# Hobots-A-Coach-405.net
KiCad netlist of a schematic drawn in Altium Designer
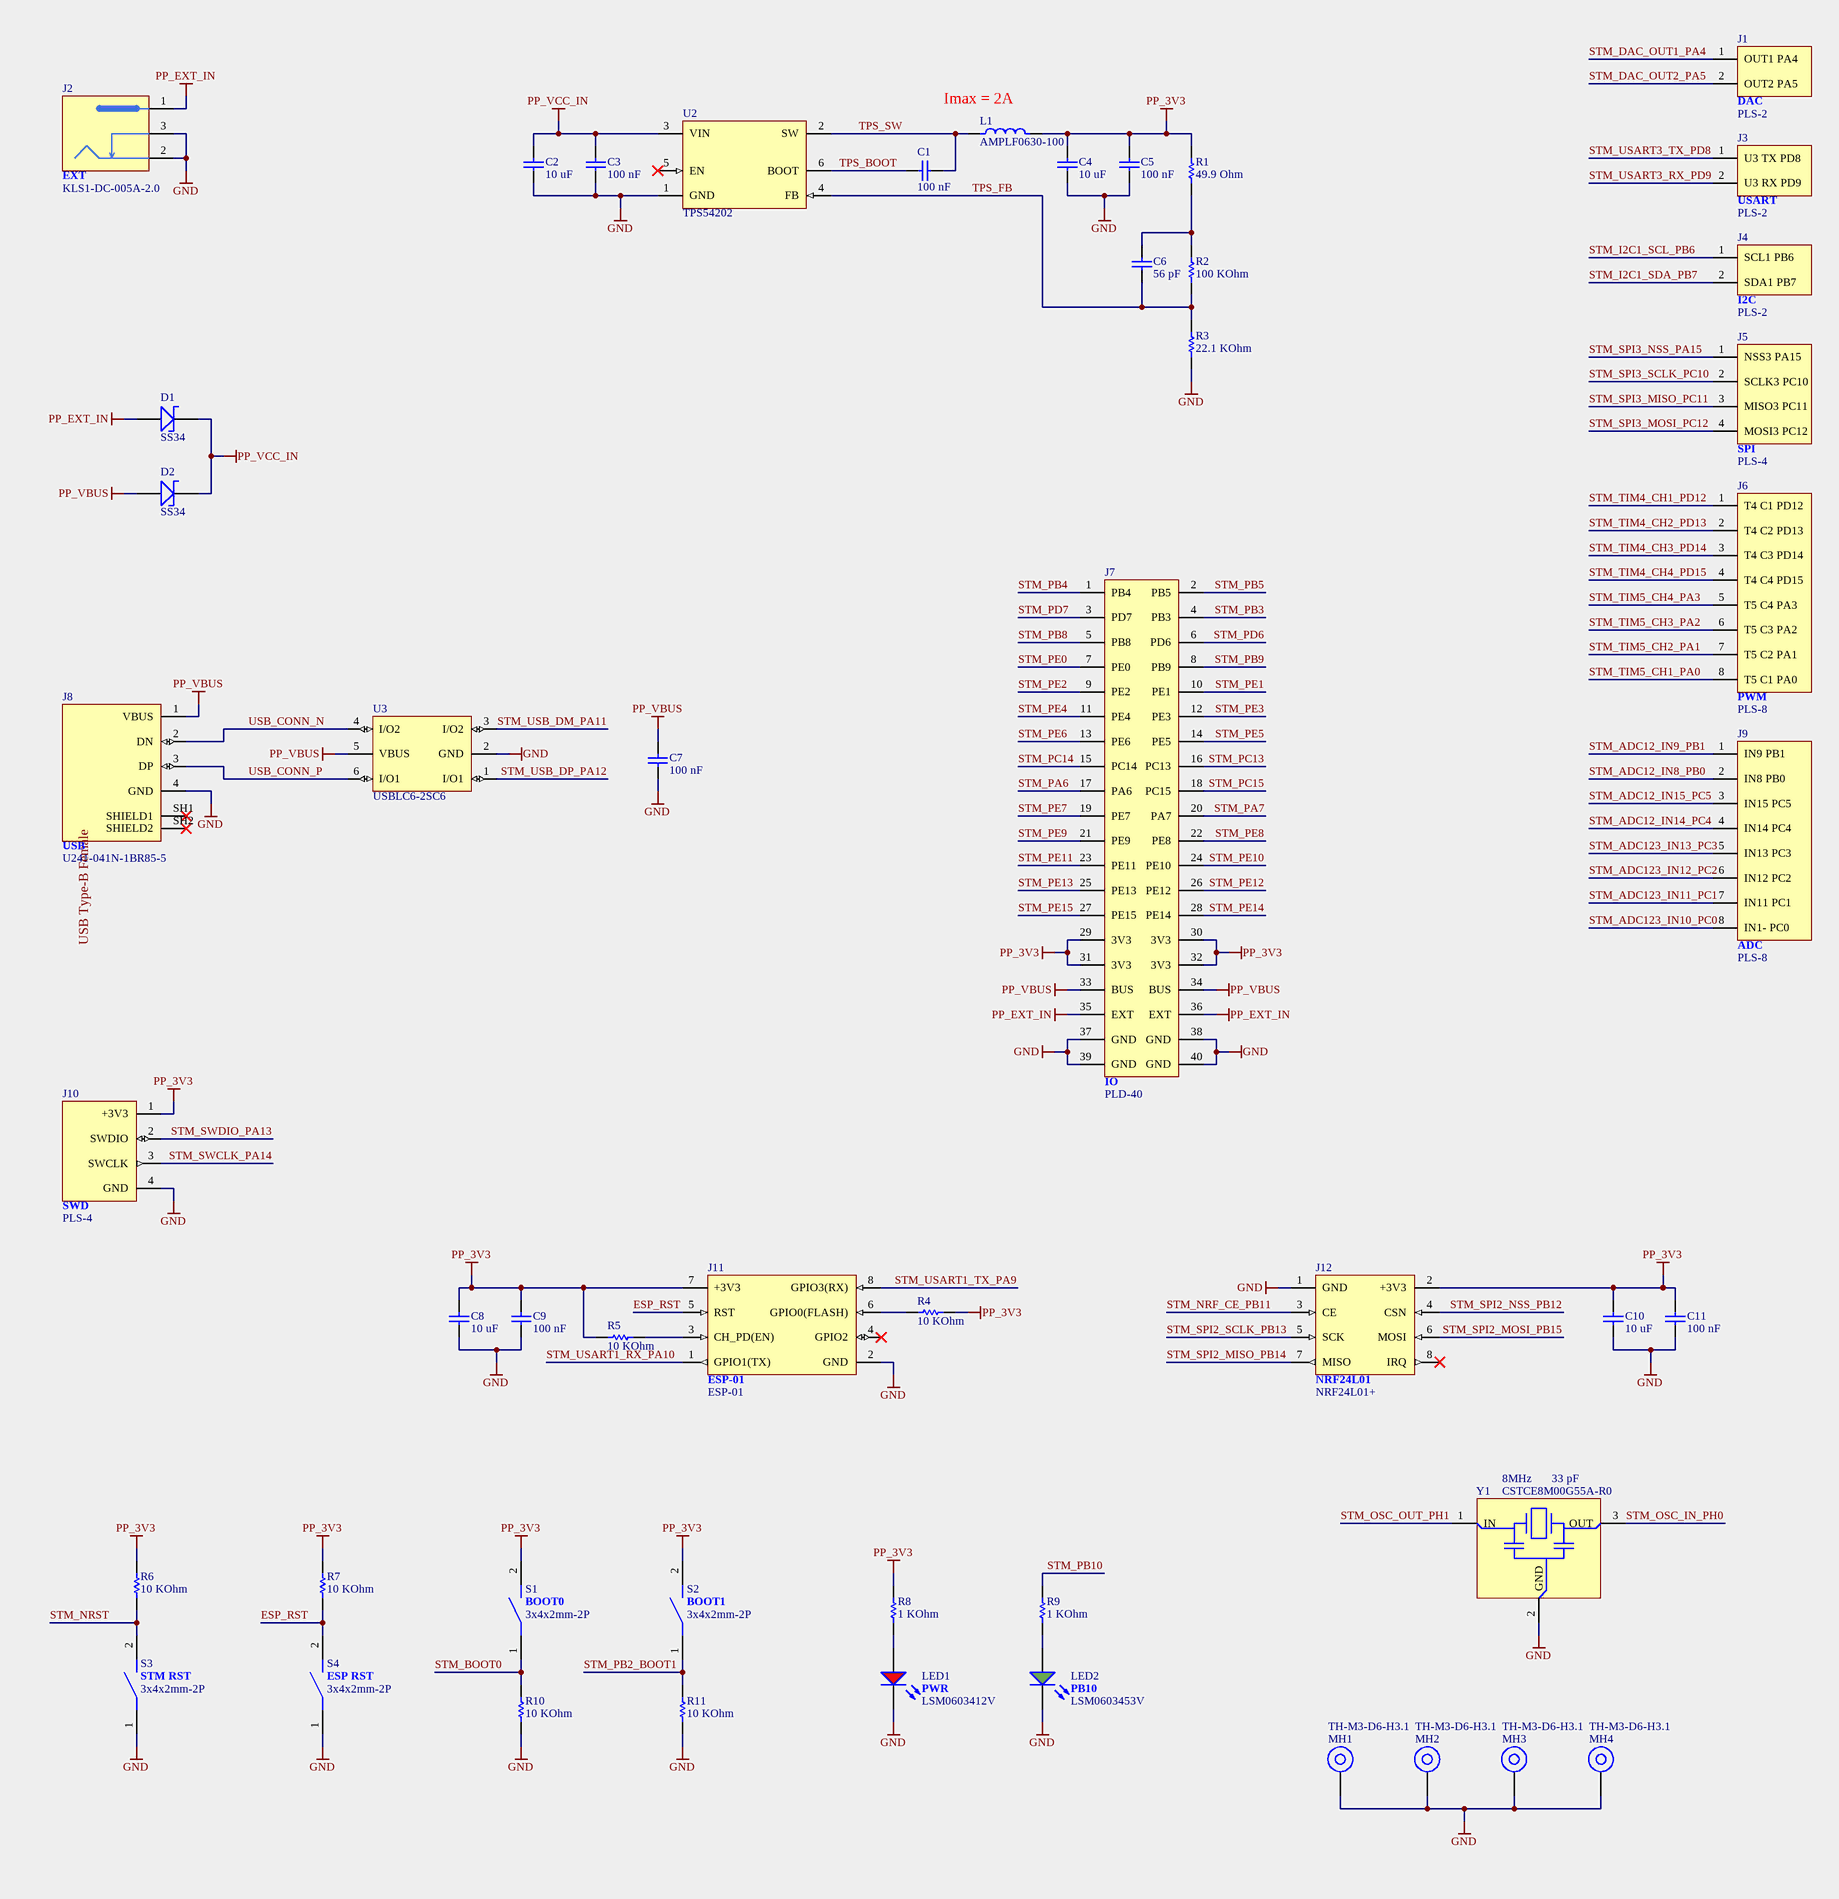
[diagram p0: Hobots-A-Coach-405.SchDoc, left]
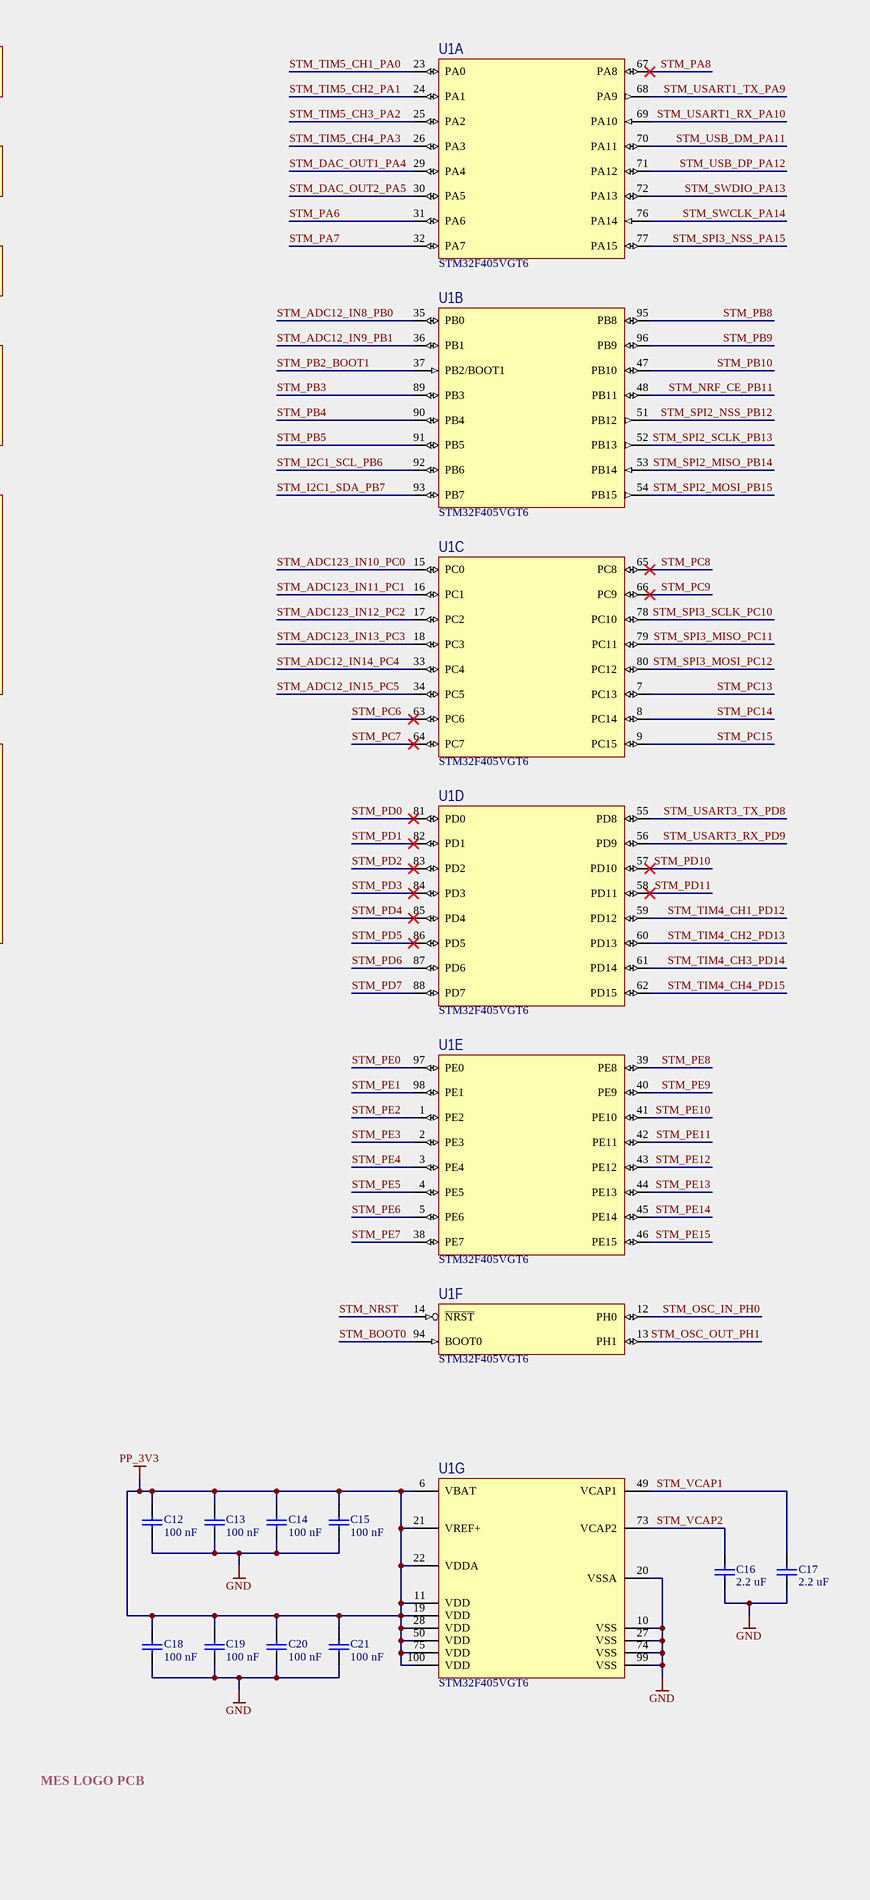
[diagram p1: Hobots-A-Coach-405.SchDoc, right]

(export (version "E")
  (design (tool "Eeschema 10.0.6"))
  (components
    (comp (ref "C1")
      (value "CAP-100N")
      (footprint "CAPC0603")
      (description "Chip Capacitor, 100 nF, +/- 5%")
      (fields (field (name "TOLERANCE") "5 %") (field (name "CAPACITANCE") "100 nF"))
      (libsource (lib "Конденсаторы керамические SMD") (part "CAP-100N"))
    )
    (comp (ref "C2")
      (value "CAP-10U")
      (footprint "CAPC0603")
      (description "Chip Capacitor, 10 uF, +/- 5%")
      (fields (field (name "TOLERANCE") "5 %") (field (name "CAPACITANCE") "10 uF"))
      (libsource (lib "Конденсаторы керамические SMD") (part "CAP-10U"))
    )
    (comp (ref "C3")
      (value "CAP-100N")
      (footprint "CAPC0603")
      (description "Chip Capacitor, 100 nF, +/- 5%")
      (fields (field (name "TOLERANCE") "5 %") (field (name "CAPACITANCE") "100 nF"))
      (libsource (lib "Конденсаторы керамические SMD") (part "CAP-100N"))
    )
    (comp (ref "C4")
      (value "CAP-10U")
      (footprint "CAPC0603")
      (description "Chip Capacitor, 10 uF, +/- 5%")
      (fields (field (name "TOLERANCE") "5 %") (field (name "CAPACITANCE") "10 uF"))
      (libsource (lib "Конденсаторы керамические SMD") (part "CAP-10U"))
    )
    (comp (ref "C5")
      (value "CAP-100N")
      (footprint "CAPC0603")
      (description "Chip Capacitor, 100 nF, +/- 5%")
      (fields (field (name "TOLERANCE") "5 %") (field (name "CAPACITANCE") "100 nF"))
      (libsource (lib "Конденсаторы керамические SMD") (part "CAP-100N"))
    )
    (comp (ref "C6")
      (value "CAP-56P")
      (footprint "CAPC0603")
      (description "Chip Capacitor, 56 pF, +/- 5%")
      (fields (field (name "TOLERANCE") "5 %") (field (name "CAPACITANCE") "56 pF"))
      (libsource (lib "Конденсаторы керамические SMD") (part "CAP-56P"))
    )
    (comp (ref "C7")
      (value "CAP-100N")
      (footprint "CAPC0603")
      (description "Chip Capacitor, 100 nF, +/- 5%")
      (fields (field (name "TOLERANCE") "5 %") (field (name "CAPACITANCE") "100 nF"))
      (libsource (lib "Конденсаторы керамические SMD") (part "CAP-100N"))
    )
    (comp (ref "C8")
      (value "CAP-10U")
      (footprint "CAPC0603")
      (description "Chip Capacitor, 10 uF, +/- 5%")
      (fields (field (name "TOLERANCE") "5 %") (field (name "CAPACITANCE") "10 uF"))
      (libsource (lib "Конденсаторы керамические SMD") (part "CAP-10U"))
    )
    (comp (ref "C9")
      (value "CAP-100N")
      (footprint "CAPC0603")
      (description "Chip Capacitor, 100 nF, +/- 5%")
      (fields (field (name "TOLERANCE") "5 %") (field (name "CAPACITANCE") "100 nF"))
      (libsource (lib "Конденсаторы керамические SMD") (part "CAP-100N"))
    )
    (comp (ref "C10")
      (value "CAP-10U")
      (footprint "CAPC0603")
      (description "Chip Capacitor, 10 uF, +/- 5%")
      (fields (field (name "TOLERANCE") "5 %") (field (name "CAPACITANCE") "10 uF"))
      (libsource (lib "Конденсаторы керамические SMD") (part "CAP-10U"))
    )
    (comp (ref "C11")
      (value "CAP-100N")
      (footprint "CAPC0603")
      (description "Chip Capacitor, 100 nF, +/- 5%")
      (fields (field (name "TOLERANCE") "5 %") (field (name "CAPACITANCE") "100 nF"))
      (libsource (lib "Конденсаторы керамические SMD") (part "CAP-100N"))
    )
    (comp (ref "C12")
      (value "CAP-100N")
      (footprint "CAPC0603")
      (description "Chip Capacitor, 100 nF, +/- 5%")
      (fields (field (name "TOLERANCE") "5 %") (field (name "CAPACITANCE") "100 nF"))
      (libsource (lib "Конденсаторы керамические SMD") (part "CAP-100N"))
    )
    (comp (ref "C13")
      (value "CAP-100N")
      (footprint "CAPC0603")
      (description "Chip Capacitor, 100 nF, +/- 5%")
      (fields (field (name "TOLERANCE") "5 %") (field (name "CAPACITANCE") "100 nF"))
      (libsource (lib "Конденсаторы керамические SMD") (part "CAP-100N"))
    )
    (comp (ref "C14")
      (value "CAP-100N")
      (footprint "CAPC0603")
      (description "Chip Capacitor, 100 nF, +/- 5%")
      (fields (field (name "TOLERANCE") "5 %") (field (name "CAPACITANCE") "100 nF"))
      (libsource (lib "Конденсаторы керамические SMD") (part "CAP-100N"))
    )
    (comp (ref "C15")
      (value "CAP-100N")
      (footprint "CAPC0603")
      (description "Chip Capacitor, 100 nF, +/- 5%")
      (fields (field (name "TOLERANCE") "5 %") (field (name "CAPACITANCE") "100 nF"))
      (libsource (lib "Конденсаторы керамические SMD") (part "CAP-100N"))
    )
    (comp (ref "C16")
      (value "CAP-2U2")
      (footprint "CAPC0603")
      (description "Chip Capacitor, 2.2 uF, +/- 5")
      (fields (field (name "TOLERANCE") "5 %") (field (name "CAPACITANCE") "2.2 uF"))
      (libsource (lib "Конденсаторы керамические SMD") (part "CAP-2U2"))
    )
    (comp (ref "C17")
      (value "CAP-2U2")
      (footprint "CAPC0603")
      (description "Chip Capacitor, 2.2 uF, +/- 5")
      (fields (field (name "TOLERANCE") "5 %") (field (name "CAPACITANCE") "2.2 uF"))
      (libsource (lib "Конденсаторы керамические SMD") (part "CAP-2U2"))
    )
    (comp (ref "C18")
      (value "CAP-100N")
      (footprint "CAPC0603")
      (description "Chip Capacitor, 100 nF, +/- 5%")
      (fields (field (name "TOLERANCE") "5 %") (field (name "CAPACITANCE") "100 nF"))
      (libsource (lib "Конденсаторы керамические SMD") (part "CAP-100N"))
    )
    (comp (ref "C19")
      (value "CAP-100N")
      (footprint "CAPC0603")
      (description "Chip Capacitor, 100 nF, +/- 5%")
      (fields (field (name "TOLERANCE") "5 %") (field (name "CAPACITANCE") "100 nF"))
      (libsource (lib "Конденсаторы керамические SMD") (part "CAP-100N"))
    )
    (comp (ref "C20")
      (value "CAP-100N")
      (footprint "CAPC0603")
      (description "Chip Capacitor, 100 nF, +/- 5%")
      (fields (field (name "TOLERANCE") "5 %") (field (name "CAPACITANCE") "100 nF"))
      (libsource (lib "Конденсаторы керамические SMD") (part "CAP-100N"))
    )
    (comp (ref "C21")
      (value "CAP-100N")
      (footprint "CAPC0603")
      (description "Chip Capacitor, 100 nF, +/- 5%")
      (fields (field (name "TOLERANCE") "5 %") (field (name "CAPACITANCE") "100 nF"))
      (libsource (lib "Конденсаторы керамические SMD") (part "CAP-100N"))
    )
    (comp (ref "D1")
      (value "SS34")
      (footprint "DO-214AC(SMA)")
      (description "40V 3A Low forward voltage drop. High current capability Schottky Diode.")
      (fields (field (name "PARTNUMBER") "SS34"))
      (libsource (lib "Диоды выпрямительные") (part "SS34"))
    )
    (comp (ref "D2")
      (value "SS34")
      (footprint "DO-214AC(SMA)")
      (description "40V 3A Low forward voltage drop. High current capability Schottky Diode.")
      (fields (field (name "PARTNUMBER") "SS34"))
      (libsource (lib "Диоды выпрямительные") (part "SS34"))
    )
    (comp (ref "G1")
      (value "MES Logo")
      (footprint "MES_LOGO_COPPER_3MM")
      (description "Logotips MES GROUP")
      (libsource (lib "Знаки") (part "MES Logo"))
    )
    (comp (ref "J1")
      (value "DAC")
      (footprint "PLS-2")
      (description "pitch 2.54")
      (fields (field (name "PARTNUMBER") "PLS-2"))
      (libsource (lib "Разъемы") (part "PLS-2"))
    )
    (comp (ref "J2")
      (value "EXT")
      (footprint "KLS1-DC-005")
      (description "5.5mm 2.0mm 2A 16V")
      (fields (field (name "PARTNUMBER") "KLS1-DC-005A-2.0"))
      (libsource (lib "Разъемы") (part "KLS1-DC-005A-2.0"))
    )
    (comp (ref "J3")
      (value "USART")
      (footprint "PLS-2")
      (description "pitch 2.54")
      (fields (field (name "PARTNUMBER") "PLS-2"))
      (libsource (lib "Разъемы") (part "PLS-2"))
    )
    (comp (ref "J4")
      (value "I2C")
      (footprint "PLS-2")
      (description "pitch 2.54")
      (fields (field (name "PARTNUMBER") "PLS-2"))
      (libsource (lib "Разъемы") (part "PLS-2"))
    )
    (comp (ref "J5")
      (value "SPI")
      (footprint "PLS-4")
      (description "pitch 2.54")
      (fields (field (name "PARTNUMBER") "PLS-4"))
      (libsource (lib "Разъемы") (part "PLS-4"))
    )
    (comp (ref "J6")
      (value "PWM")
      (footprint "PLS-8")
      (description "pitch 2.54")
      (fields (field (name "PARTNUMBER") "PLS-8"))
      (libsource (lib "Разъемы") (part "PLS-8"))
    )
    (comp (ref "J7")
      (value "IO")
      (footprint "PLD-40")
      (description "2 row, pitch 2.54")
      (fields (field (name "PARTNUMBER") "PLD-40"))
      (libsource (lib "Разъемы") (part "PLD-40"))
    )
    (comp (ref "J8")
      (value "USB")
      (footprint "U241-041N-1BR85-5")
      (description "USB - Type B Female USB 2 4 Through Hole USB Connectors")
      (fields (field (name "PARTNUMBER") "U241-041N-1BR85-5"))
      (libsource (lib "Разъемы") (part "USB-B U241-041N-1BR85-5"))
    )
    (comp (ref "J9")
      (value "ADC")
      (footprint "PLS-8")
      (description "pitch 2.54")
      (fields (field (name "PARTNUMBER") "PLS-8"))
      (libsource (lib "Разъемы") (part "PLS-8"))
    )
    (comp (ref "J10")
      (value "SWD")
      (footprint "PLS-4")
      (description "STM SWD 4 pin")
      (fields (field (name "PARTNUMBER") "PLS-4"))
      (libsource (lib "Разъемы") (part "SWD-PLS4"))
    )
    (comp (ref "J11")
      (value "ESP-01")
      (footprint "ESP-01 Socket")
      (description "Socket for ESP8266 ESP-01 Connector PBD 8 pins 2x4 pitch 2.54")
      (fields (field (name "PARTNUMBER") "ESP-01"))
      (libsource (lib "Разъемы") (part "ESP-01 Socket"))
    )
    (comp (ref "J12")
      (value "NRF24L01")
      (footprint "NRF24L01+ Socket")
      (description "Socket for NRF24L01 / NRF24L01+ Connector PBD 8 pins 2x4 pitch 2.54")
      (fields (field (name "PARTNUMBER") "NRF24L01+"))
      (libsource (lib "Разъемы") (part "NRF24L01+ Socket"))
    )
    (comp (ref "L1")
      (value "AMPLF0630-100")
      (footprint "AMPLF0630")
      (description "Shielded Power Inductor 10μH ± 20%")
      (fields (field (name "PARTNUMBER") "AMPLF0630-100"))
      (libsource (lib "Индуктивности") (part "AMPLF0630-100"))
    )
    (comp (ref "LED1")
      (value "PWR")
      (footprint "LSM0603-Series")
      (description "Red LED 0603 2V 20mA")
      (fields (field (name "PARTNUMBER") "LSM0603412V"))
      (libsource (lib "Светодиоды") (part "LSM0603412V"))
    )
    (comp (ref "LED2")
      (value "PB10")
      (footprint "LSM0603-Series")
      (description "Green LED 0603 3V 20mA")
      (fields (field (name "PARTNUMBER") "LSM0603453V"))
      (libsource (lib "Светодиоды") (part "LSM0603453V"))
    )
    (comp (ref "MH1")
      (value "TH-M3-D6-H3.1")
      (footprint "TH-M3-D6-H3.1")
      (libsource (lib "Отверстия") (part "TH-M3-D6-H3.1"))
    )
    (comp (ref "MH2")
      (value "TH-M3-D6-H3.1")
      (footprint "TH-M3-D6-H3.1")
      (libsource (lib "Отверстия") (part "TH-M3-D6-H3.1"))
    )
    (comp (ref "MH3")
      (value "TH-M3-D6-H3.1")
      (footprint "TH-M3-D6-H3.1")
      (libsource (lib "Отверстия") (part "TH-M3-D6-H3.1"))
    )
    (comp (ref "MH4")
      (value "TH-M3-D6-H3.1")
      (footprint "TH-M3-D6-H3.1")
      (libsource (lib "Отверстия") (part "TH-M3-D6-H3.1"))
    )
    (comp (ref "R1")
      (value "RES-49R9")
      (footprint "RES0603")
      (description "Chip Resistor, 49.9 Ohm, +/- 1%")
      (fields (field (name "TOLERANCE") "1 %") (field (name "RESISTANCE") "49.9 Ohm"))
      (libsource (lib "Резисторы SMD") (part "RES-49R9"))
    )
    (comp (ref "R2")
      (value "RES-100K")
      (footprint "RES0603")
      (description "Chip Resistor, 100 KOhm, +/- 1%")
      (fields (field (name "TOLERANCE") "1 %") (field (name "RESISTANCE") "100 KOhm"))
      (libsource (lib "Резисторы SMD") (part "RES-100K"))
    )
    (comp (ref "R3")
      (value "RES-22K1")
      (footprint "RES0603")
      (description "Chip Resistor, 22.1 KOhm, +/- 1%")
      (fields (field (name "TOLERANCE") "1 %") (field (name "RESISTANCE") "22.1 KOhm"))
      (libsource (lib "Резисторы SMD") (part "RES-22K1"))
    )
    (comp (ref "R4")
      (value "RES-10K")
      (footprint "RES0603")
      (description "Chip Resistor, 10 KOhm, +/- 1%")
      (fields (field (name "TOLERANCE") "1 %") (field (name "RESISTANCE") "10 KOhm"))
      (libsource (lib "Резисторы SMD") (part "RES-10K"))
    )
    (comp (ref "R5")
      (value "RES-10K")
      (footprint "RES0603")
      (description "Chip Resistor, 10 KOhm, +/- 1%")
      (fields (field (name "TOLERANCE") "1 %") (field (name "RESISTANCE") "10 KOhm"))
      (libsource (lib "Резисторы SMD") (part "RES-10K"))
    )
    (comp (ref "R6")
      (value "RES-10K")
      (footprint "RES0603")
      (description "Chip Resistor, 10 KOhm, +/- 1%")
      (fields (field (name "TOLERANCE") "1 %") (field (name "RESISTANCE") "10 KOhm"))
      (libsource (lib "Резисторы SMD") (part "RES-10K"))
    )
    (comp (ref "R7")
      (value "RES-10K")
      (footprint "RES0603")
      (description "Chip Resistor, 10 KOhm, +/- 1%")
      (fields (field (name "TOLERANCE") "1 %") (field (name "RESISTANCE") "10 KOhm"))
      (libsource (lib "Резисторы SMD") (part "RES-10K"))
    )
    (comp (ref "R8")
      (value "RES-1K")
      (footprint "RES0603")
      (description "Chip Resistor, 1 KOhm, +/- 1%")
      (fields (field (name "TOLERANCE") "1 %") (field (name "RESISTANCE") "1 KOhm"))
      (libsource (lib "Резисторы SMD") (part "RES-1K"))
    )
    (comp (ref "R9")
      (value "RES-1K")
      (footprint "RES0603")
      (description "Chip Resistor, 1 KOhm, +/- 1%")
      (fields (field (name "TOLERANCE") "1 %") (field (name "RESISTANCE") "1 KOhm"))
      (libsource (lib "Резисторы SMD") (part "RES-1K"))
    )
    (comp (ref "R10")
      (value "RES-10K")
      (footprint "RES0603")
      (description "Chip Resistor, 10 KOhm, +/- 1%")
      (fields (field (name "TOLERANCE") "1 %") (field (name "RESISTANCE") "10 KOhm"))
      (libsource (lib "Резисторы SMD") (part "RES-10K"))
    )
    (comp (ref "R11")
      (value "RES-10K")
      (footprint "RES0603")
      (description "Chip Resistor, 10 KOhm, +/- 1%")
      (fields (field (name "TOLERANCE") "1 %") (field (name "RESISTANCE") "10 KOhm"))
      (libsource (lib "Резисторы SMD") (part "RES-10K"))
    )
    (comp (ref "S1")
      (value "BOOT0")
      (footprint "Tactile Switch SMD 3x4x2-2p")
      (description "2-Pin SMD Tactile Switch, sunrom 3x4x2mm 12V DC 0.2A")
      (fields (field (name "MODEL") "3x4x2mm-2P"))
      (libsource (lib "Кнопки") (part "Tactile Switch 2P 3x4x2"))
    )
    (comp (ref "S2")
      (value "BOOT1")
      (footprint "Tactile Switch SMD 3x4x2-2p")
      (description "2-Pin SMD Tactile Switch, sunrom 3x4x2mm 12V DC 0.2A")
      (fields (field (name "MODEL") "3x4x2mm-2P"))
      (libsource (lib "Кнопки") (part "Tactile Switch 2P 3x4x2"))
    )
    (comp (ref "S3")
      (value "STM RST")
      (footprint "Tactile Switch SMD 3x4x2-2p")
      (description "2-Pin SMD Tactile Switch, sunrom 3x4x2mm 12V DC 0.2A")
      (fields (field (name "MODEL") "3x4x2mm-2P"))
      (libsource (lib "Кнопки") (part "Tactile Switch 2P 3x4x2"))
    )
    (comp (ref "S4")
      (value "ESP RST")
      (footprint "Tactile Switch SMD 3x4x2-2p")
      (description "2-Pin SMD Tactile Switch, sunrom 3x4x2mm 12V DC 0.2A")
      (fields (field (name "MODEL") "3x4x2mm-2P"))
      (libsource (lib "Кнопки") (part "Tactile Switch 2P 3x4x2"))
    )
    (comp (ref "U1")
      (value "STM32F405VGT6")
      (footprint "LQFP-100-STM32")
      (description "1024 KB Flash 192 RAM 168 MHz ARM based 32-bit MCU")
      (fields (field (name "PARTNUMBER") "STM32F405VGT6"))
      (libsource (lib "Микроконтроллеры") (part "STM32F405VGT6"))
    )
    (comp (ref "U2")
      (value "TPS54202")
      (footprint "SOT23-6-TI-TPS54202")
      (description "4.5-V to 28-V Input, 2-A Output, EMI Friendly\r\nSynchronous Step Down Converter")
      (fields (field (name "PARTNUMBER") "TPS54202"))
      (libsource (lib "Регуляторы напряжения") (part "TPS54202"))
    )
    (comp (ref "U3")
      (value "USBLC6-2SC6")
      (footprint "SOT23-6L-STM")
      (fields (field (name "PARTNUMBER") "USBLC6-2SC6"))
      (libsource (lib "Диоды TVS") (part "USBLC6-2SC6"))
    )
    (comp (ref "Y1")
      (value "CSTCE8M00G55A-R0")
      (footprint "MURATA_3213")
      (description "8MHz ±0.5% 33pF 40 Ohm(Max) SMDCrystal Resonators")
      (fields
        (field (name "LOADCAPACITANCE") "33 pF")
        (field (name "FREQUENCY") "8MHz")
        (field (name "PARTNUMBER") "CSTCE8M00G55A-R0")
      )
      (libsource (lib "Кварцы") (part "CSTCE8M00G55A-R0"))
    )
  )
  (nets
    (net (code "1") (name "/ESP_RST") (class "Default")
      (node (ref "J11") (pin "5") (pinfunction "RST_5") (pintype "input"))
      (node (ref "R7") (pin "1") (pinfunction "1_1") (pintype "passive"))
      (node (ref "S4") (pin "2") (pintype "passive"))
    )
    (net (code "2") (name "/STM_ADC12_IN8_PB0") (class "Default")
      (node (ref "J9") (pin "2") (pinfunction "T4_C2_PD13_2") (pintype "passive"))
      (node (ref "U1") (pin "35") (pinfunction "PB0_35") (pintype "bidirectional"))
    )
    (net (code "3") (name "/STM_ADC12_IN9_PB1") (class "Default")
      (node (ref "J9") (pin "1") (pinfunction "T4_C1_PD12_1") (pintype "passive"))
      (node (ref "U1") (pin "36") (pinfunction "PB1_36") (pintype "bidirectional"))
    )
    (net (code "4") (name "/STM_ADC12_IN14_PC4") (class "Default")
      (node (ref "J9") (pin "4") (pinfunction "T4_C4_PD15_4") (pintype "passive"))
      (node (ref "U1") (pin "33") (pinfunction "PC4_33") (pintype "bidirectional"))
    )
    (net (code "5") (name "/STM_ADC12_IN15_PC5") (class "Default")
      (node (ref "J9") (pin "3") (pinfunction "T4_C3_PD14_3") (pintype "passive"))
      (node (ref "U1") (pin "34") (pinfunction "PC5_34") (pintype "bidirectional"))
    )
    (net (code "6") (name "/STM_ADC123_IN10_PC0") (class "Default")
      (node (ref "J9") (pin "8") (pinfunction "T5_C1_PA0_8") (pintype "passive"))
      (node (ref "U1") (pin "15") (pinfunction "PC0_15") (pintype "bidirectional"))
    )
    (net (code "7") (name "/STM_ADC123_IN11_PC1") (class "Default")
      (node (ref "J9") (pin "7") (pinfunction "T5_C2_PA1_7") (pintype "passive"))
      (node (ref "U1") (pin "16") (pinfunction "PC1_16") (pintype "bidirectional"))
    )
    (net (code "8") (name "/STM_ADC123_IN12_PC2") (class "Default")
      (node (ref "J9") (pin "6") (pinfunction "T5_C3_PA2_6") (pintype "passive"))
      (node (ref "U1") (pin "17") (pinfunction "PC2_17") (pintype "bidirectional"))
    )
    (net (code "9") (name "/STM_ADC123_IN13_PC3") (class "Default")
      (node (ref "J9") (pin "5") (pinfunction "T5_C4_PA3_5") (pintype "passive"))
      (node (ref "U1") (pin "18") (pinfunction "PC3_18") (pintype "bidirectional"))
    )
    (net (code "10") (name "/STM_BOOT0") (class "Default")
      (node (ref "R10") (pin "2") (pinfunction "2_2") (pintype "passive"))
      (node (ref "S1") (pin "1") (pintype "passive"))
      (node (ref "U1") (pin "94") (pinfunction "BOOT0_94") (pintype "input"))
    )
    (net (code "11") (name "/STM_DAC_OUT1_PA4") (class "Default")
      (node (ref "J1") (pin "1") (pinfunction "SCL1_PB6_1") (pintype "passive"))
      (node (ref "U1") (pin "29") (pinfunction "PA4_29") (pintype "bidirectional"))
    )
    (net (code "12") (name "/STM_DAC_OUT2_PA5") (class "Default")
      (node (ref "J1") (pin "2") (pinfunction "SDA1_PB7_2") (pintype "passive"))
      (node (ref "U1") (pin "30") (pinfunction "PA5_30") (pintype "bidirectional"))
    )
    (net (code "13") (name "/STM_I2C1_SCL_PB6") (class "Default")
      (node (ref "J4") (pin "1") (pinfunction "SCL1_PB6_1") (pintype "passive"))
      (node (ref "U1") (pin "92") (pinfunction "PB6_92") (pintype "bidirectional"))
    )
    (net (code "14") (name "/STM_I2C1_SDA_PB7") (class "Default")
      (node (ref "J4") (pin "2") (pinfunction "SDA1_PB7_2") (pintype "passive"))
      (node (ref "U1") (pin "93") (pinfunction "PB7_93") (pintype "bidirectional"))
    )
    (net (code "15") (name "/STM_NRF_CE_PB11") (class "Default")
      (node (ref "J12") (pin "3") (pinfunction "CE_3") (pintype "input"))
      (node (ref "U1") (pin "48") (pinfunction "PB11_48") (pintype "bidirectional"))
    )
    (net (code "16") (name "/STM_NRST") (class "Default")
      (node (ref "R6") (pin "1") (pinfunction "1_1") (pintype "passive"))
      (node (ref "S3") (pin "2") (pintype "passive"))
      (node (ref "U1") (pin "14") (pinfunction "~{NRST}_14") (pintype "input"))
    )
    (net (code "17") (name "/STM_OSC_IN_PH0") (class "Default")
      (node (ref "U1") (pin "12") (pinfunction "PH0_12") (pintype "bidirectional"))
      (node (ref "Y1") (pin "3") (pinfunction "OUT_3") (pintype "passive"))
    )
    (net (code "18") (name "/STM_OSC_OUT_PH1") (class "Default")
      (node (ref "U1") (pin "13") (pinfunction "PH1_13") (pintype "bidirectional"))
      (node (ref "Y1") (pin "1") (pinfunction "IN_1") (pintype "passive"))
    )
    (net (code "19") (name "/STM_PA6") (class "Default")
      (node (ref "J7") (pin "17") (pinfunction "PA6_17") (pintype "passive"))
      (node (ref "U1") (pin "31") (pinfunction "PA6_31") (pintype "bidirectional"))
    )
    (net (code "20") (name "/STM_PA7") (class "Default")
      (node (ref "J7") (pin "20") (pinfunction "PA7_20") (pintype "passive"))
      (node (ref "U1") (pin "32") (pinfunction "PA7_32") (pintype "bidirectional"))
    )
    (net (code "21") (name "/STM_PA8") (class "Default")
      (node (ref "U1") (pin "67") (pinfunction "PA8_67") (pintype "bidirectional+no_connect"))
    )
    (net (code "22") (name "/STM_PB2_BOOT1") (class "Default")
      (node (ref "R11") (pin "2") (pinfunction "2_2") (pintype "passive"))
      (node (ref "S2") (pin "1") (pintype "passive"))
      (node (ref "U1") (pin "37") (pinfunction "PB2/BOOT1_37") (pintype "bidirectional"))
    )
    (net (code "23") (name "/STM_PB3") (class "Default")
      (node (ref "J7") (pin "4") (pinfunction "PB3_4") (pintype "passive"))
      (node (ref "U1") (pin "89") (pinfunction "PB3_89") (pintype "bidirectional"))
    )
    (net (code "24") (name "/STM_PB4") (class "Default")
      (node (ref "J7") (pin "1") (pinfunction "PB4_1") (pintype "passive"))
      (node (ref "U1") (pin "90") (pinfunction "PB4_90") (pintype "bidirectional"))
    )
    (net (code "25") (name "/STM_PB5") (class "Default")
      (node (ref "J7") (pin "2") (pinfunction "PB5_2") (pintype "passive"))
      (node (ref "U1") (pin "91") (pinfunction "PB5_91") (pintype "bidirectional"))
    )
    (net (code "26") (name "/STM_PB8") (class "Default")
      (node (ref "J7") (pin "5") (pinfunction "PB8_5") (pintype "passive"))
      (node (ref "U1") (pin "95") (pinfunction "PB8_95") (pintype "bidirectional"))
    )
    (net (code "27") (name "/STM_PB9") (class "Default")
      (node (ref "J7") (pin "8") (pinfunction "PB9_8") (pintype "passive"))
      (node (ref "U1") (pin "96") (pinfunction "PB9_96") (pintype "bidirectional"))
    )
    (net (code "28") (name "/STM_PB10") (class "Default")
      (node (ref "R9") (pin "2") (pinfunction "2_2") (pintype "passive"))
      (node (ref "U1") (pin "47") (pinfunction "PB10_47") (pintype "bidirectional"))
    )
    (net (code "29") (name "/STM_PC6") (class "Default")
      (node (ref "U1") (pin "63") (pinfunction "PC6_63") (pintype "bidirectional+no_connect"))
    )
    (net (code "30") (name "/STM_PC7") (class "Default")
      (node (ref "U1") (pin "64") (pinfunction "PC7_64") (pintype "bidirectional+no_connect"))
    )
    (net (code "31") (name "/STM_PC8") (class "Default")
      (node (ref "U1") (pin "65") (pinfunction "PC8_65") (pintype "bidirectional+no_connect"))
    )
    (net (code "32") (name "/STM_PC9") (class "Default")
      (node (ref "U1") (pin "66") (pinfunction "PC9_66") (pintype "bidirectional+no_connect"))
    )
    (net (code "33") (name "/STM_PC13") (class "Default")
      (node (ref "J7") (pin "16") (pinfunction "PC13_16") (pintype "passive"))
      (node (ref "U1") (pin "7") (pinfunction "PC13_7") (pintype "bidirectional"))
    )
    (net (code "34") (name "/STM_PC14") (class "Default")
      (node (ref "J7") (pin "15") (pinfunction "PC14_15") (pintype "passive"))
      (node (ref "U1") (pin "8") (pinfunction "PC14_8") (pintype "bidirectional"))
    )
    (net (code "35") (name "/STM_PC15") (class "Default")
      (node (ref "J7") (pin "18") (pinfunction "PC15_18") (pintype "passive"))
      (node (ref "U1") (pin "9") (pinfunction "PC15_9") (pintype "bidirectional"))
    )
    (net (code "36") (name "/STM_PD0") (class "Default")
      (node (ref "U1") (pin "81") (pinfunction "PD0_81") (pintype "bidirectional+no_connect"))
    )
    (net (code "37") (name "/STM_PD1") (class "Default")
      (node (ref "U1") (pin "82") (pinfunction "PD1_82") (pintype "bidirectional+no_connect"))
    )
    (net (code "38") (name "/STM_PD2") (class "Default")
      (node (ref "U1") (pin "83") (pinfunction "PD2_83") (pintype "bidirectional+no_connect"))
    )
    (net (code "39") (name "/STM_PD3") (class "Default")
      (node (ref "U1") (pin "84") (pinfunction "PD3_84") (pintype "bidirectional+no_connect"))
    )
    (net (code "40") (name "/STM_PD4") (class "Default")
      (node (ref "U1") (pin "85") (pinfunction "PD4_85") (pintype "bidirectional+no_connect"))
    )
    (net (code "41") (name "/STM_PD5") (class "Default")
      (node (ref "U1") (pin "86") (pinfunction "PD5_86") (pintype "bidirectional+no_connect"))
    )
    (net (code "42") (name "/STM_PD6") (class "Default")
      (node (ref "J7") (pin "6") (pinfunction "PD6_6") (pintype "passive"))
      (node (ref "U1") (pin "87") (pinfunction "PD6_87") (pintype "bidirectional"))
    )
    (net (code "43") (name "/STM_PD7") (class "Default")
      (node (ref "J7") (pin "3") (pinfunction "PD7_3") (pintype "passive"))
      (node (ref "U1") (pin "88") (pinfunction "PD7_88") (pintype "bidirectional"))
    )
    (net (code "44") (name "/STM_PD10") (class "Default")
      (node (ref "U1") (pin "57") (pinfunction "PD10_57") (pintype "bidirectional+no_connect"))
    )
    (net (code "45") (name "/STM_PD11") (class "Default")
      (node (ref "U1") (pin "58") (pinfunction "PD11_58") (pintype "bidirectional+no_connect"))
    )
    (net (code "46") (name "/STM_PE0") (class "Default")
      (node (ref "J7") (pin "7") (pinfunction "PE0_7") (pintype "passive"))
      (node (ref "U1") (pin "97") (pinfunction "PE0_97") (pintype "bidirectional"))
    )
    (net (code "47") (name "/STM_PE1") (class "Default")
      (node (ref "J7") (pin "10") (pinfunction "PE1_10") (pintype "passive"))
      (node (ref "U1") (pin "98") (pinfunction "PE1_98") (pintype "bidirectional"))
    )
    (net (code "48") (name "/STM_PE2") (class "Default")
      (node (ref "J7") (pin "9") (pinfunction "PE2_9") (pintype "passive"))
      (node (ref "U1") (pin "1") (pinfunction "PE2_1") (pintype "bidirectional"))
    )
    (net (code "49") (name "/STM_PE3") (class "Default")
      (node (ref "J7") (pin "12") (pinfunction "PE3_12") (pintype "passive"))
      (node (ref "U1") (pin "2") (pinfunction "PE3_2") (pintype "bidirectional"))
    )
    (net (code "50") (name "/STM_PE4") (class "Default")
      (node (ref "J7") (pin "11") (pinfunction "PE4_11") (pintype "passive"))
      (node (ref "U1") (pin "3") (pinfunction "PE4_3") (pintype "bidirectional"))
    )
    (net (code "51") (name "/STM_PE5") (class "Default")
      (node (ref "J7") (pin "14") (pinfunction "PE5_14") (pintype "passive"))
      (node (ref "U1") (pin "4") (pinfunction "PE5_4") (pintype "bidirectional"))
    )
    (net (code "52") (name "/STM_PE6") (class "Default")
      (node (ref "J7") (pin "13") (pinfunction "PE6_13") (pintype "passive"))
      (node (ref "U1") (pin "5") (pinfunction "PE6_5") (pintype "bidirectional"))
    )
    (net (code "53") (name "/STM_PE7") (class "Default")
      (node (ref "J7") (pin "19") (pinfunction "PE7_19") (pintype "passive"))
      (node (ref "U1") (pin "38") (pinfunction "PE7_38") (pintype "bidirectional"))
    )
    (net (code "54") (name "/STM_PE8") (class "Default")
      (node (ref "J7") (pin "22") (pinfunction "PE8_22") (pintype "passive"))
      (node (ref "U1") (pin "39") (pinfunction "PE8_39") (pintype "bidirectional"))
    )
    (net (code "55") (name "/STM_PE9") (class "Default")
      (node (ref "J7") (pin "21") (pinfunction "PE9_21") (pintype "passive"))
      (node (ref "U1") (pin "40") (pinfunction "PE9_40") (pintype "bidirectional"))
    )
    (net (code "56") (name "/STM_PE10") (class "Default")
      (node (ref "J7") (pin "24") (pinfunction "PE10_24") (pintype "passive"))
      (node (ref "U1") (pin "41") (pinfunction "PE10_41") (pintype "bidirectional"))
    )
    (net (code "57") (name "/STM_PE11") (class "Default")
      (node (ref "J7") (pin "23") (pinfunction "PE11_23") (pintype "passive"))
      (node (ref "U1") (pin "42") (pinfunction "PE11_42") (pintype "bidirectional"))
    )
    (net (code "58") (name "/STM_PE12") (class "Default")
      (node (ref "J7") (pin "26") (pinfunction "PE12_26") (pintype "passive"))
      (node (ref "U1") (pin "43") (pinfunction "PE12_43") (pintype "bidirectional"))
    )
    (net (code "59") (name "/STM_PE13") (class "Default")
      (node (ref "J7") (pin "25") (pinfunction "PE13_25") (pintype "passive"))
      (node (ref "U1") (pin "44") (pinfunction "PE13_44") (pintype "bidirectional"))
    )
    (net (code "60") (name "/STM_PE14") (class "Default")
      (node (ref "J7") (pin "28") (pinfunction "PE14_28") (pintype "passive"))
      (node (ref "U1") (pin "45") (pinfunction "PE14_45") (pintype "bidirectional"))
    )
    (net (code "61") (name "/STM_PE15") (class "Default")
      (node (ref "J7") (pin "27") (pinfunction "PE15_27") (pintype "passive"))
      (node (ref "U1") (pin "46") (pinfunction "PE15_46") (pintype "bidirectional"))
    )
    (net (code "62") (name "/STM_SPI2_MISO_PB14") (class "Default")
      (node (ref "J12") (pin "7") (pinfunction "MISO_7") (pintype "output"))
      (node (ref "U1") (pin "53") (pinfunction "PB14_53") (pintype "bidirectional"))
    )
    (net (code "63") (name "/STM_SPI2_MOSI_PB15") (class "Default")
      (node (ref "J12") (pin "6") (pinfunction "MOSI_6") (pintype "input"))
      (node (ref "U1") (pin "54") (pinfunction "PB15_54") (pintype "bidirectional"))
    )
    (net (code "64") (name "/STM_SPI2_NSS_PB12") (class "Default")
      (node (ref "J12") (pin "4") (pinfunction "CSN_4") (pintype "input"))
      (node (ref "U1") (pin "51") (pinfunction "PB12_51") (pintype "bidirectional"))
    )
    (net (code "65") (name "/STM_SPI2_SCLK_PB13") (class "Default")
      (node (ref "J12") (pin "5") (pinfunction "SCK_5") (pintype "input"))
      (node (ref "U1") (pin "52") (pinfunction "PB13_52") (pintype "bidirectional"))
    )
    (net (code "66") (name "/STM_SPI3_MISO_PC11") (class "Default")
      (node (ref "J5") (pin "3") (pinfunction "MISO3_PC11_3") (pintype "passive"))
      (node (ref "U1") (pin "79") (pinfunction "PC11_79") (pintype "bidirectional"))
    )
    (net (code "67") (name "/STM_SPI3_MOSI_PC12") (class "Default")
      (node (ref "J5") (pin "4") (pinfunction "MOSI3_PC12_4") (pintype "passive"))
      (node (ref "U1") (pin "80") (pinfunction "PC12_80") (pintype "bidirectional"))
    )
    (net (code "68") (name "/STM_SPI3_NSS_PA15") (class "Default")
      (node (ref "J5") (pin "1") (pinfunction "NSS3_PA15_1") (pintype "passive"))
      (node (ref "U1") (pin "77") (pinfunction "PA15_77") (pintype "bidirectional"))
    )
    (net (code "69") (name "/STM_SPI3_SCLK_PC10") (class "Default")
      (node (ref "J5") (pin "2") (pinfunction "SCLK3_PC10_2") (pintype "passive"))
      (node (ref "U1") (pin "78") (pinfunction "PC10_78") (pintype "bidirectional"))
    )
    (net (code "70") (name "/STM_SWCLK_PA14") (class "Default")
      (node (ref "J10") (pin "3") (pinfunction "SWCLK_3") (pintype "output"))
      (node (ref "U1") (pin "76") (pinfunction "PA14_76") (pintype "bidirectional"))
    )
    (net (code "71") (name "/STM_SWDIO_PA13") (class "Default")
      (node (ref "J10") (pin "2") (pinfunction "SWDIO_2") (pintype "bidirectional"))
      (node (ref "U1") (pin "72") (pinfunction "PA13_72") (pintype "bidirectional"))
    )
    (net (code "72") (name "/STM_TIM4_CH1_PD12") (class "Default")
      (node (ref "J6") (pin "1") (pinfunction "T4_C1_PD12_1") (pintype "passive"))
      (node (ref "U1") (pin "59") (pinfunction "PD12_59") (pintype "bidirectional"))
    )
    (net (code "73") (name "/STM_TIM4_CH2_PD13") (class "Default")
      (node (ref "J6") (pin "2") (pinfunction "T4_C2_PD13_2") (pintype "passive"))
      (node (ref "U1") (pin "60") (pinfunction "PD13_60") (pintype "bidirectional"))
    )
    (net (code "74") (name "/STM_TIM4_CH3_PD14") (class "Default")
      (node (ref "J6") (pin "3") (pinfunction "T4_C3_PD14_3") (pintype "passive"))
      (node (ref "U1") (pin "61") (pinfunction "PD14_61") (pintype "bidirectional"))
    )
    (net (code "75") (name "/STM_TIM4_CH4_PD15") (class "Default")
      (node (ref "J6") (pin "4") (pinfunction "T4_C4_PD15_4") (pintype "passive"))
      (node (ref "U1") (pin "62") (pinfunction "PD15_62") (pintype "bidirectional"))
    )
    (net (code "76") (name "/STM_TIM5_CH1_PA0") (class "Default")
      (node (ref "J6") (pin "8") (pinfunction "T5_C1_PA0_8") (pintype "passive"))
      (node (ref "U1") (pin "23") (pinfunction "PA0_23") (pintype "bidirectional"))
    )
    (net (code "77") (name "/STM_TIM5_CH2_PA1") (class "Default")
      (node (ref "J6") (pin "7") (pinfunction "T5_C2_PA1_7") (pintype "passive"))
      (node (ref "U1") (pin "24") (pinfunction "PA1_24") (pintype "bidirectional"))
    )
    (net (code "78") (name "/STM_TIM5_CH3_PA2") (class "Default")
      (node (ref "J6") (pin "6") (pinfunction "T5_C3_PA2_6") (pintype "passive"))
      (node (ref "U1") (pin "25") (pinfunction "PA2_25") (pintype "bidirectional"))
    )
    (net (code "79") (name "/STM_TIM5_CH4_PA3") (class "Default")
      (node (ref "J6") (pin "5") (pinfunction "T5_C4_PA3_5") (pintype "passive"))
      (node (ref "U1") (pin "26") (pinfunction "PA3_26") (pintype "bidirectional"))
    )
    (net (code "80") (name "/STM_USART1_RX_PA10") (class "Default")
      (node (ref "J11") (pin "1") (pinfunction "GPIO1(TX)_1") (pintype "output"))
      (node (ref "U1") (pin "69") (pinfunction "PA10_69") (pintype "bidirectional"))
    )
    (net (code "81") (name "/STM_USART1_TX_PA9") (class "Default")
      (node (ref "J11") (pin "8") (pinfunction "GPIO3(RX)_8") (pintype "input"))
      (node (ref "U1") (pin "68") (pinfunction "PA9_68") (pintype "bidirectional"))
    )
    (net (code "82") (name "/STM_USART3_RX_PD9") (class "Default")
      (node (ref "J3") (pin "2") (pinfunction "SDA1_PB7_2") (pintype "passive"))
      (node (ref "U1") (pin "56") (pinfunction "PD9_56") (pintype "bidirectional"))
    )
    (net (code "83") (name "/STM_USART3_TX_PD8") (class "Default")
      (node (ref "J3") (pin "1") (pinfunction "SCL1_PB6_1") (pintype "passive"))
      (node (ref "U1") (pin "55") (pinfunction "PD8_55") (pintype "bidirectional"))
    )
    (net (code "84") (name "/STM_USB_DM_PA11") (class "Default")
      (node (ref "U1") (pin "70") (pinfunction "PA11_70") (pintype "bidirectional"))
      (node (ref "U3") (pin "3") (pinfunction "I/O2_3") (pintype "bidirectional"))
    )
    (net (code "85") (name "/STM_USB_DP_PA12") (class "Default")
      (node (ref "U1") (pin "71") (pinfunction "PA12_71") (pintype "bidirectional"))
      (node (ref "U3") (pin "1") (pinfunction "I/O1_1") (pintype "bidirectional"))
    )
    (net (code "86") (name "/STM_VCAP1") (class "Default")
      (node (ref "C17") (pin "2") (pinfunction "2_2") (pintype "passive"))
      (node (ref "U1") (pin "49") (pinfunction "VCAP1_49") (pintype "power_in"))
    )
    (net (code "87") (name "/STM_VCAP2") (class "Default")
      (node (ref "C16") (pin "2") (pinfunction "2_2") (pintype "passive"))
      (node (ref "U1") (pin "73") (pinfunction "VCAP2_73") (pintype "power_in"))
    )
    (net (code "88") (name "/TPS_BOOT") (class "Default")
      (node (ref "C1") (pin "2") (pinfunction "2_2") (pintype "passive"))
      (node (ref "U2") (pin "6") (pinfunction "BOOT_6") (pintype "power_in"))
    )
    (net (code "89") (name "/TPS_FB") (class "Default")
      (node (ref "C6") (pin "1") (pinfunction "1_1") (pintype "passive"))
      (node (ref "R2") (pin "1") (pinfunction "1_1") (pintype "passive"))
      (node (ref "R3") (pin "2") (pinfunction "2_2") (pintype "passive"))
      (node (ref "U2") (pin "4") (pinfunction "FB_4") (pintype "input"))
    )
    (net (code "90") (name "/TPS_SW") (class "Default")
      (node (ref "C1") (pin "1") (pinfunction "1_1") (pintype "passive"))
      (node (ref "L1") (pin "2") (pinfunction "2_2") (pintype "passive"))
      (node (ref "U2") (pin "2") (pinfunction "SW_2") (pintype "power_in"))
    )
    (net (code "91") (name "/USB_CONN_N") (class "Default")
      (node (ref "J8") (pin "2") (pinfunction "DN_2") (pintype "bidirectional"))
      (node (ref "U3") (pin "4") (pinfunction "I/O2_4") (pintype "bidirectional"))
    )
    (net (code "92") (name "/USB_CONN_P") (class "Default")
      (node (ref "J8") (pin "3") (pinfunction "DP_3") (pintype "bidirectional"))
      (node (ref "U3") (pin "6") (pinfunction "I/O1_6") (pintype "bidirectional"))
    )
    (net (code "93") (name "GND") (class "Default")
      (node (ref "C10") (pin "1") (pinfunction "1_1") (pintype "passive"))
      (node (ref "C11") (pin "1") (pinfunction "1_1") (pintype "passive"))
      (node (ref "C12") (pin "1") (pinfunction "1_1") (pintype "passive"))
      (node (ref "C13") (pin "1") (pinfunction "1_1") (pintype "passive"))
      (node (ref "C14") (pin "1") (pinfunction "1_1") (pintype "passive"))
      (node (ref "C15") (pin "1") (pinfunction "1_1") (pintype "passive"))
      (node (ref "C16") (pin "1") (pinfunction "1_1") (pintype "passive"))
      (node (ref "C17") (pin "1") (pinfunction "1_1") (pintype "passive"))
      (node (ref "C18") (pin "1") (pinfunction "1_1") (pintype "passive"))
      (node (ref "C19") (pin "1") (pinfunction "1_1") (pintype "passive"))
      (node (ref "C2") (pin "1") (pinfunction "1_1") (pintype "passive"))
      (node (ref "C20") (pin "1") (pinfunction "1_1") (pintype "passive"))
      (node (ref "C21") (pin "1") (pinfunction "1_1") (pintype "passive"))
      (node (ref "C3") (pin "1") (pinfunction "1_1") (pintype "passive"))
      (node (ref "C4") (pin "1") (pinfunction "1_1") (pintype "passive"))
      (node (ref "C5") (pin "1") (pinfunction "1_1") (pintype "passive"))
      (node (ref "C7") (pin "1") (pinfunction "1_1") (pintype "passive"))
      (node (ref "C8") (pin "1") (pinfunction "1_1") (pintype "passive"))
      (node (ref "C9") (pin "1") (pinfunction "1_1") (pintype "passive"))
      (node (ref "J10") (pin "4") (pinfunction "GND_4") (pintype "power_in"))
      (node (ref "J11") (pin "2") (pinfunction "GND_2") (pintype "power_in"))
      (node (ref "J12") (pin "1") (pinfunction "GND_1") (pintype "power_in"))
      (node (ref "J2") (pin "2") (pinfunction "%_2") (pintype "passive"))
      (node (ref "J2") (pin "3") (pinfunction "%_3") (pintype "passive"))
      (node (ref "J7") (pin "37") (pinfunction "GND_37") (pintype "passive"))
      (node (ref "J7") (pin "38") (pinfunction "GND_38") (pintype "passive"))
      (node (ref "J7") (pin "39") (pinfunction "GND_39") (pintype "passive"))
      (node (ref "J7") (pin "40") (pinfunction "GND_40") (pintype "passive"))
      (node (ref "J8") (pin "4") (pinfunction "GND_4") (pintype "power_in"))
      (node (ref "LED1") (pin "1") (pinfunction "K_1") (pintype "passive"))
      (node (ref "LED2") (pin "1") (pinfunction "K_1") (pintype "passive"))
      (node (ref "MH1") (pin "PTH") (pintype "passive"))
      (node (ref "MH2") (pin "PTH") (pintype "passive"))
      (node (ref "MH3") (pin "PTH") (pintype "passive"))
      (node (ref "MH4") (pin "PTH") (pintype "passive"))
      (node (ref "R10") (pin "1") (pinfunction "1_1") (pintype "passive"))
      (node (ref "R11") (pin "1") (pinfunction "1_1") (pintype "passive"))
      (node (ref "R3") (pin "1") (pinfunction "1_1") (pintype "passive"))
      (node (ref "S3") (pin "1") (pintype "passive"))
      (node (ref "S4") (pin "1") (pintype "passive"))
      (node (ref "U1") (pin "10") (pinfunction "VSS_10") (pintype "power_in"))
      (node (ref "U1") (pin "20") (pinfunction "VSSA_20") (pintype "power_in"))
      (node (ref "U1") (pin "27") (pinfunction "VSS_27") (pintype "power_in"))
      (node (ref "U1") (pin "74") (pinfunction "VSS_74") (pintype "power_in"))
      (node (ref "U1") (pin "99") (pinfunction "VSS_99") (pintype "power_in"))
      (node (ref "U2") (pin "1") (pinfunction "GND_1") (pintype "power_in"))
      (node (ref "U3") (pin "2") (pinfunction "GND_2") (pintype "power_in"))
      (node (ref "Y1") (pin "2") (pinfunction "GND_2") (pintype "passive"))
    )
    (net (code "94") (name "Net-(C6-Pad2)") (class "Default")
      (node (ref "C6") (pin "2") (pinfunction "2_2") (pintype "passive"))
      (node (ref "R1") (pin "1") (pinfunction "1_1") (pintype "passive"))
      (node (ref "R2") (pin "2") (pinfunction "2_2") (pintype "passive"))
    )
    (net (code "95") (name "Net-(J11-CH_PD(EN))") (class "Default")
      (node (ref "J11") (pin "3") (pinfunction "CH_PD(EN)_3") (pintype "input"))
      (node (ref "R5") (pin "1") (pinfunction "1_1") (pintype "passive"))
    )
    (net (code "96") (name "Net-(J11-GPIO0(FLASH))") (class "Default")
      (node (ref "J11") (pin "6") (pinfunction "GPIO0(FLASH)_6") (pintype "input"))
      (node (ref "R4") (pin "2") (pinfunction "2_2") (pintype "passive"))
    )
    (net (code "97") (name "Net-(LED1-A)") (class "Default")
      (node (ref "LED1") (pin "2") (pinfunction "A_2") (pintype "passive"))
      (node (ref "R8") (pin "1") (pinfunction "1_1") (pintype "passive"))
    )
    (net (code "98") (name "Net-(LED2-A)") (class "Default")
      (node (ref "LED2") (pin "2") (pinfunction "A_2") (pintype "passive"))
      (node (ref "R9") (pin "1") (pinfunction "1_1") (pintype "passive"))
    )
    (net (code "99") (name "PP_3V3") (class "Default")
      (node (ref "C10") (pin "2") (pinfunction "2_2") (pintype "passive"))
      (node (ref "C11") (pin "2") (pinfunction "2_2") (pintype "passive"))
      (node (ref "C12") (pin "2") (pinfunction "2_2") (pintype "passive"))
      (node (ref "C13") (pin "2") (pinfunction "2_2") (pintype "passive"))
      (node (ref "C14") (pin "2") (pinfunction "2_2") (pintype "passive"))
      (node (ref "C15") (pin "2") (pinfunction "2_2") (pintype "passive"))
      (node (ref "C18") (pin "2") (pinfunction "2_2") (pintype "passive"))
      (node (ref "C19") (pin "2") (pinfunction "2_2") (pintype "passive"))
      (node (ref "C20") (pin "2") (pinfunction "2_2") (pintype "passive"))
      (node (ref "C21") (pin "2") (pinfunction "2_2") (pintype "passive"))
      (node (ref "C4") (pin "2") (pinfunction "2_2") (pintype "passive"))
      (node (ref "C5") (pin "2") (pinfunction "2_2") (pintype "passive"))
      (node (ref "C8") (pin "2") (pinfunction "2_2") (pintype "passive"))
      (node (ref "C9") (pin "2") (pinfunction "2_2") (pintype "passive"))
      (node (ref "J10") (pin "1") (pinfunction "+3V3_1") (pintype "power_in"))
      (node (ref "J11") (pin "7") (pinfunction "+3V3_7") (pintype "power_in"))
      (node (ref "J12") (pin "2") (pinfunction "+3V3_2") (pintype "power_in"))
      (node (ref "J7") (pin "29") (pinfunction "3V3_29") (pintype "passive"))
      (node (ref "J7") (pin "30") (pinfunction "3V3_30") (pintype "passive"))
      (node (ref "J7") (pin "31") (pinfunction "3V3_31") (pintype "passive"))
      (node (ref "J7") (pin "32") (pinfunction "3V3_32") (pintype "passive"))
      (node (ref "L1") (pin "1") (pinfunction "1_1") (pintype "passive"))
      (node (ref "R1") (pin "2") (pinfunction "2_2") (pintype "passive"))
      (node (ref "R4") (pin "1") (pinfunction "1_1") (pintype "passive"))
      (node (ref "R5") (pin "2") (pinfunction "2_2") (pintype "passive"))
      (node (ref "R6") (pin "2") (pinfunction "2_2") (pintype "passive"))
      (node (ref "R7") (pin "2") (pinfunction "2_2") (pintype "passive"))
      (node (ref "R8") (pin "2") (pinfunction "2_2") (pintype "passive"))
      (node (ref "S1") (pin "2") (pintype "passive"))
      (node (ref "S2") (pin "2") (pintype "passive"))
      (node (ref "U1") (pin "100") (pinfunction "VDD_100") (pintype "power_in"))
      (node (ref "U1") (pin "11") (pinfunction "VDD_11") (pintype "power_in"))
      (node (ref "U1") (pin "19") (pinfunction "VDD_19") (pintype "power_in"))
      (node (ref "U1") (pin "21") (pinfunction "VREF+_21") (pintype "power_in"))
      (node (ref "U1") (pin "22") (pinfunction "VDDA_22") (pintype "power_in"))
      (node (ref "U1") (pin "28") (pinfunction "VDD_28") (pintype "power_in"))
      (node (ref "U1") (pin "50") (pinfunction "VDD_50") (pintype "power_in"))
      (node (ref "U1") (pin "6") (pinfunction "VBAT_6") (pintype "power_in"))
      (node (ref "U1") (pin "75") (pinfunction "VDD_75") (pintype "power_in"))
    )
    (net (code "100") (name "PP_EXT_IN") (class "Default")
      (node (ref "D1") (pin "2") (pinfunction "A_2") (pintype "passive"))
      (node (ref "J2") (pin "1") (pinfunction "%_1") (pintype "passive"))
      (node (ref "J7") (pin "35") (pinfunction "EXT_35") (pintype "passive"))
      (node (ref "J7") (pin "36") (pinfunction "EXT_36") (pintype "passive"))
    )
    (net (code "101") (name "PP_VBUS") (class "Default")
      (node (ref "C7") (pin "2") (pinfunction "2_2") (pintype "passive"))
      (node (ref "D2") (pin "2") (pinfunction "A_2") (pintype "passive"))
      (node (ref "J7") (pin "33") (pinfunction "BUS_33") (pintype "passive"))
      (node (ref "J7") (pin "34") (pinfunction "BUS_34") (pintype "passive"))
      (node (ref "J8") (pin "1") (pinfunction "VBUS_1") (pintype "power_in"))
      (node (ref "U3") (pin "5") (pinfunction "VBUS_5") (pintype "power_in"))
    )
    (net (code "102") (name "PP_VCC_IN") (class "Default")
      (node (ref "C2") (pin "2") (pinfunction "2_2") (pintype "passive"))
      (node (ref "C3") (pin "2") (pinfunction "2_2") (pintype "passive"))
      (node (ref "D1") (pin "1") (pinfunction "C_1") (pintype "passive"))
      (node (ref "D2") (pin "1") (pinfunction "C_1") (pintype "passive"))
      (node (ref "U2") (pin "3") (pinfunction "VIN_3") (pintype "power_in"))
    )
    (net (code "103") (name "unconnected-(J8-SHIELD1-PadSH1)") (class "Default")
      (node (ref "J8") (pin "SH1") (pinfunction "SHIELD1_SH1") (pintype "power_in+no_connect"))
    )
    (net (code "104") (name "unconnected-(J8-SHIELD2-PadSH2)") (class "Default")
      (node (ref "J8") (pin "SH2") (pinfunction "SHIELD2_SH2") (pintype "power_in+no_connect"))
    )
    (net (code "105") (name "unconnected-(J11-GPIO2-Pad4)") (class "Default")
      (node (ref "J11") (pin "4") (pinfunction "GPIO2_4") (pintype "bidirectional+no_connect"))
    )
    (net (code "106") (name "unconnected-(J12-IRQ-Pad8)") (class "Default")
      (node (ref "J12") (pin "8") (pinfunction "IRQ_8") (pintype "output+no_connect"))
    )
    (net (code "107") (name "unconnected-(U2-EN-Pad5)") (class "Default")
      (node (ref "U2") (pin "5") (pinfunction "EN_5") (pintype "input+no_connect"))
    )
  )
)
